# MCISO-S01-V00-Master.net
KiCad netlist of a schematic drawn in Altium Designer
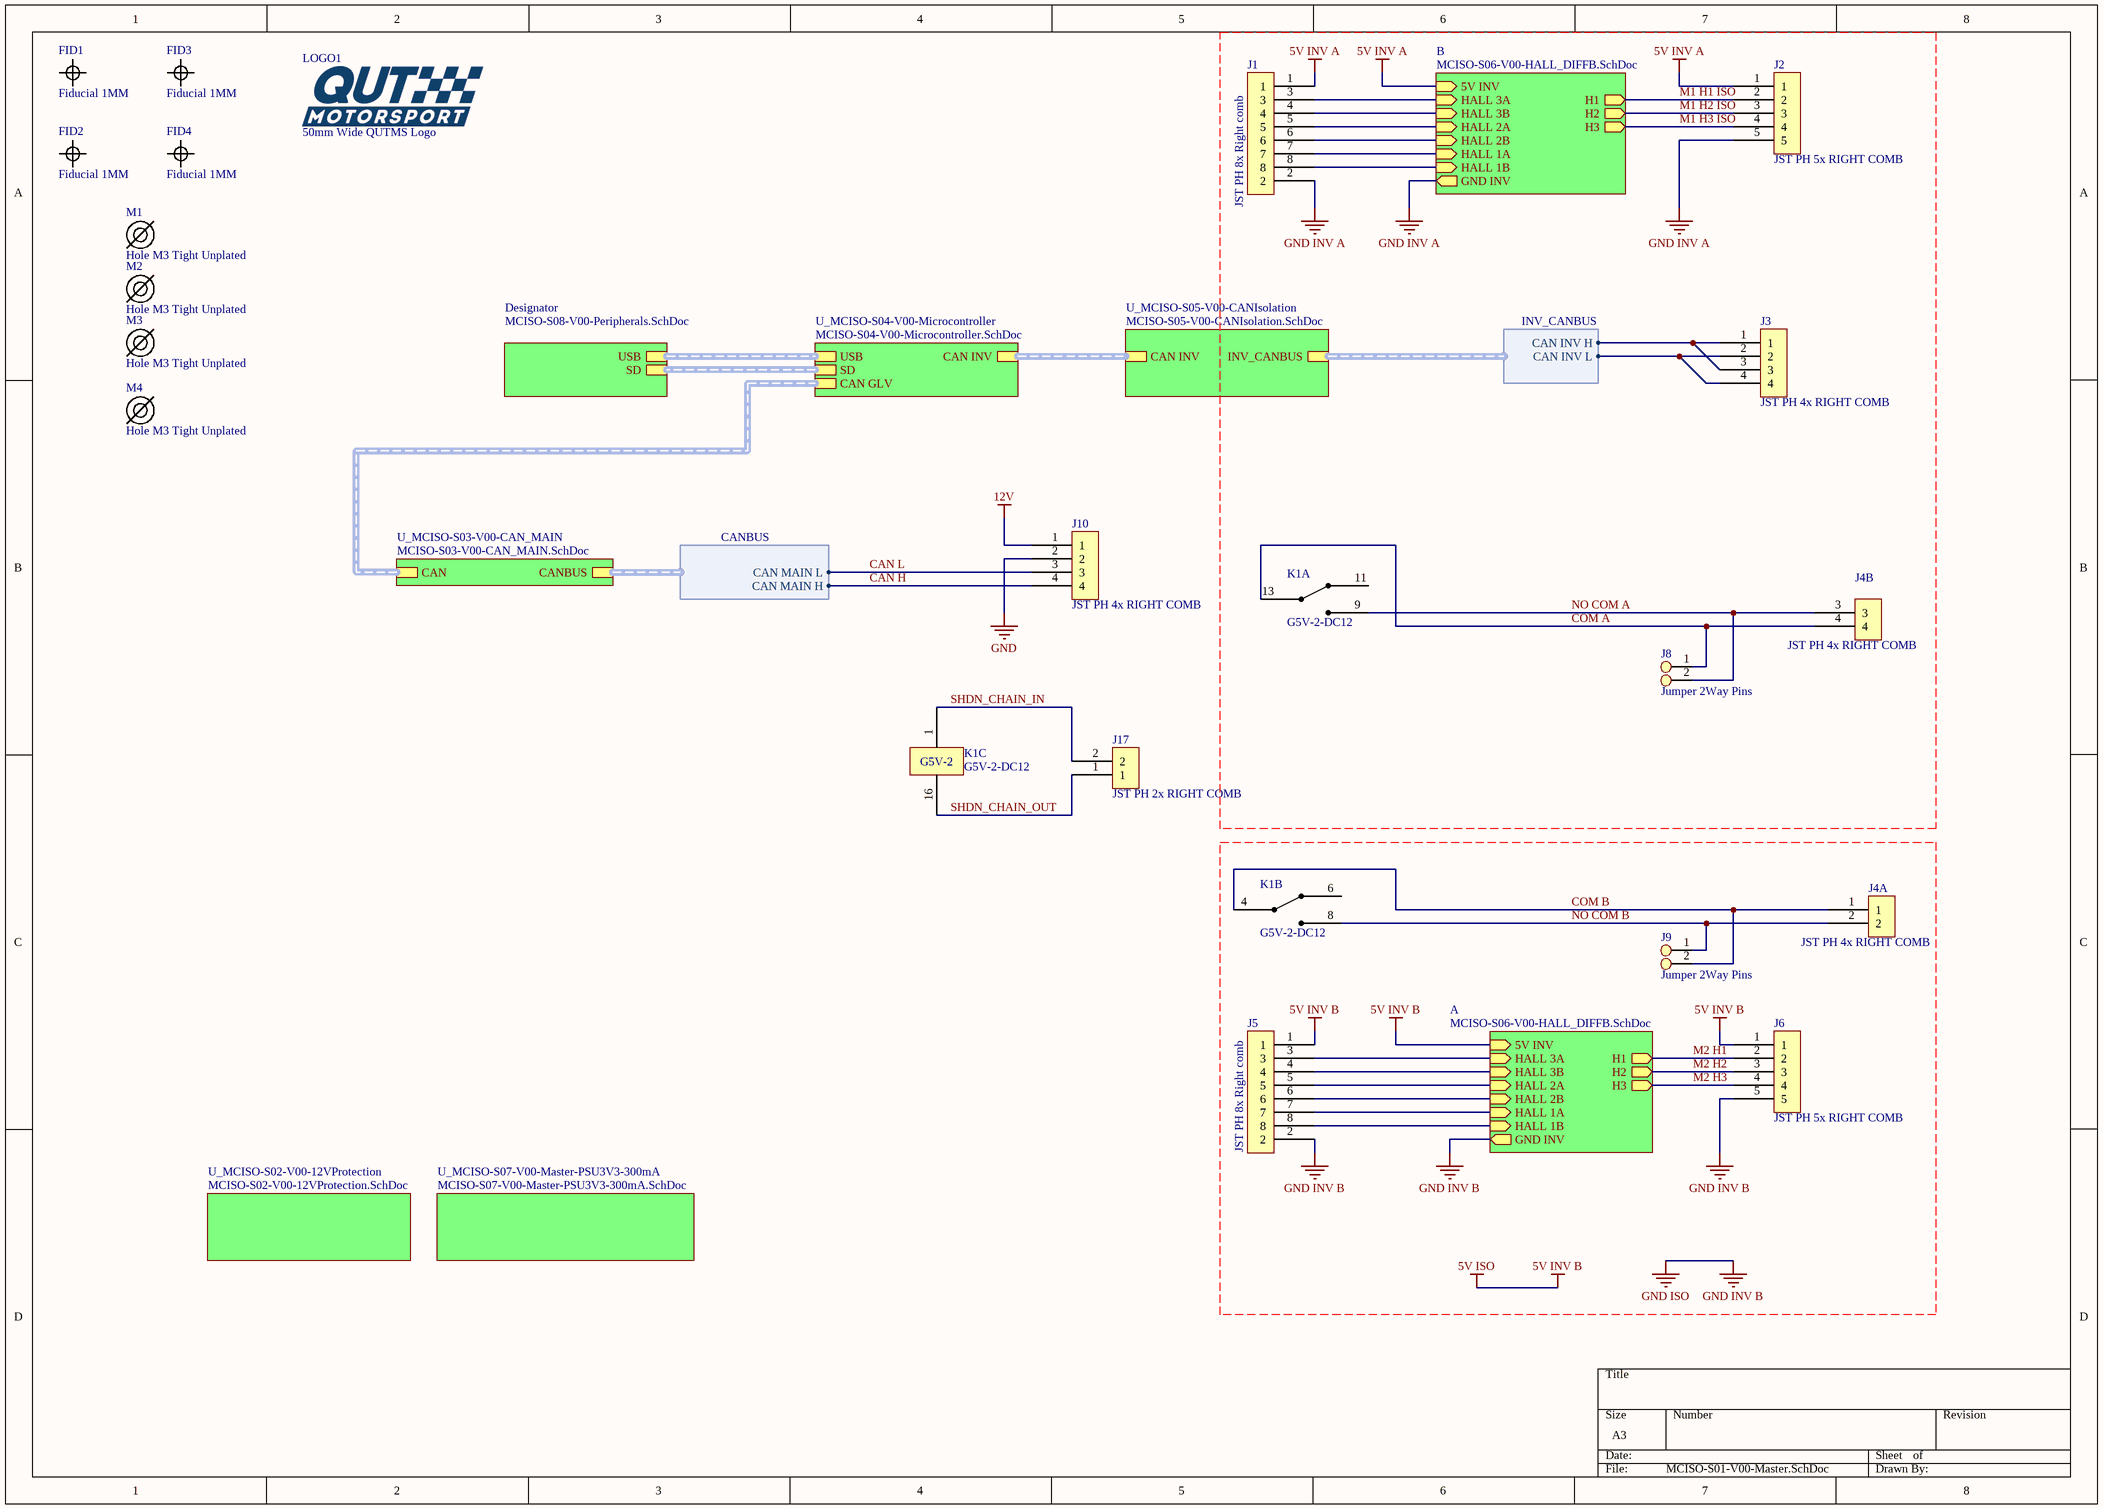
[diagram p0: MCISO-S01-V00-Master.SchDoc]

(export (version "E")
  (design (tool "Eeschema 10.0.6"))
  (components
    (comp (ref "FID1")
      (value "Fiducial 1MM")
      (footprint "FIDUCIAL 1MM")
      (libsource (lib "QUTMS-MCISOLibrary") (part "Fiducial 1MM"))
    )
    (comp (ref "FID2")
      (value "Fiducial 1MM")
      (footprint "FIDUCIAL 1MM")
      (libsource (lib "QUTMS-MCISOLibrary") (part "Fiducial 1MM"))
    )
    (comp (ref "FID3")
      (value "Fiducial 1MM")
      (footprint "FIDUCIAL 1MM")
      (libsource (lib "QUTMS-MCISOLibrary") (part "Fiducial 1MM"))
    )
    (comp (ref "FID4")
      (value "Fiducial 1MM")
      (footprint "FIDUCIAL 1MM")
      (libsource (lib "QUTMS-MCISOLibrary") (part "Fiducial 1MM"))
    )
    (comp (ref "J1")
      (value "JST PH 8x Right comb")
      (footprint "JST PH 8x RIGHT SMD")
      (libsource (lib "QUTMS-MCISOLibrary") (part "JST PH 8x Right comb"))
    )
    (comp (ref "J2")
      (value "JST PH 5x RIGHT COMB")
      (footprint "JST PH 5x RIGHT COMB")
      (libsource (lib "QUTMS-MCISOLibrary") (part "JST PH 5x RIGHT COMB"))
    )
    (comp (ref "J3")
      (value "JST PH 4x RIGHT COMB")
      (footprint "JST PH 4x RIGHT COMB")
      (libsource (lib "QUTMS-MCISOLibrary") (part "JST PH 4x RIGHT COMB"))
    )
    (comp (ref "J4")
      (value "JST PH 4x RIGHT COMB")
      (footprint "JST PH 4x RIGHT COMB")
      (libsource (lib "QUTMS-MCISOLibrary") (part "JST PH 4x RIGHT COMB_1"))
    )
    (comp (ref "J5")
      (value "JST PH 8x Right comb")
      (footprint "JST PH 8x RIGHT SMD")
      (libsource (lib "QUTMS-MCISOLibrary") (part "JST PH 8x Right comb"))
    )
    (comp (ref "J6")
      (value "JST PH 5x RIGHT COMB")
      (footprint "JST PH 5x RIGHT COMB")
      (libsource (lib "QUTMS-MCISOLibrary") (part "JST PH 5x RIGHT COMB"))
    )
    (comp (ref "J8")
      (value "Jumper 2Way Pins")
      (footprint "Jumper_2Way_Pin")
      (description "Jumper 2Way Side Pins")
      (libsource (lib "QUTMS-MCISOLibrary") (part "Jumper 2Way Side Pins"))
    )
    (comp (ref "J9")
      (value "Jumper 2Way Pins")
      (footprint "Jumper_2Way_Pin")
      (description "Jumper 2Way Side Pins")
      (libsource (lib "QUTMS-MCISOLibrary") (part "Jumper 2Way Side Pins"))
    )
    (comp (ref "J10")
      (value "JST PH 4x RIGHT COMB")
      (footprint "JST PH 4x RIGHT COMB")
      (libsource (lib "QUTMS-MCISOLibrary") (part "JST PH 4x RIGHT COMB"))
    )
    (comp (ref "J17")
      (value "JST PH 2x RIGHT COMB")
      (footprint "JST PH 2x RIGHT COMB")
      (libsource (lib "QUTMS-MCISOLibrary") (part "JST PH 2x RIGHT COMB"))
    )
    (comp (ref "K1")
      (value "G5V-2-DC12")
      (footprint "G5V-2")
      (description "General Purpose Relay DPDT (2 Form C) Through Hole, 12V, 2A")
      (libsource (lib "QUTMS-MCISOLibrary") (part "G5V-2-DC12"))
    )
    (comp (ref "LOGO1")
      (value "50mm Wide QUTMS Logo")
      (footprint "QUTMS LOGO 10MM")
      (libsource (lib "QUTMS-MCISOLibrary") (part "QUTMS Logo 50mm"))
    )
    (comp (ref "M1")
      (value "Hole M3 Tight Unplated")
      (footprint "M3.2 UNPLATED")
      (description "M3.2 Hole, No Plating")
      (libsource (lib "QUTMS-MCISOLibrary") (part "Hole M3 Tight Unplated"))
    )
    (comp (ref "M2")
      (value "Hole M3 Tight Unplated")
      (footprint "M3.2 UNPLATED")
      (description "M3.2 Hole, No Plating")
      (libsource (lib "QUTMS-MCISOLibrary") (part "Hole M3 Tight Unplated"))
    )
    (comp (ref "M3")
      (value "Hole M3 Tight Unplated")
      (footprint "M3.2 UNPLATED")
      (description "M3.2 Hole, No Plating")
      (libsource (lib "QUTMS-MCISOLibrary") (part "Hole M3 Tight Unplated"))
    )
    (comp (ref "M4")
      (value "Hole M3 Tight Unplated")
      (footprint "M3.2 UNPLATED")
      (description "M3.2 Hole, No Plating")
      (libsource (lib "QUTMS-MCISOLibrary") (part "Hole M3 Tight Unplated"))
    )
  )
  (nets
    (net (code "4") (name "/CAN H") (class "Default")
      (node (ref "J10") (pin "4") (pinfunction "4_4") (pintype "passive"))
    )
    (net (code "6") (name "/CAN L") (class "Default")
      (node (ref "J10") (pin "3") (pinfunction "3_3") (pintype "passive"))
    )
    (net (code "7") (name "/COM A") (class "Default")
      (node (ref "J4") (pin "4") (pinfunction "4_4") (pintype "passive"))
      (node (ref "J8") (pin "1") (pinfunction "1_1") (pintype "passive"))
      (node (ref "K1") (pin "13") (pinfunction "13_13") (pintype "passive"))
    )
    (net (code "8") (name "/COM B") (class "Default")
      (node (ref "J4") (pin "1") (pinfunction "1_1") (pintype "passive"))
      (node (ref "J9") (pin "2") (pinfunction "2_2") (pintype "passive"))
      (node (ref "K1") (pin "4") (pinfunction "4_4") (pintype "passive"))
    )
    (net (code "9") (name "/HALL 1A") (class "Default")
      (node (ref "J5") (pin "7") (pinfunction "7_7") (pintype "passive"))
    )
    (net (code "10") (name "/HALL 1A_1") (class "Default")
      (node (ref "J1") (pin "7") (pinfunction "7_7") (pintype "passive"))
    )
    (net (code "11") (name "/HALL 1B") (class "Default")
      (node (ref "J5") (pin "8") (pinfunction "8_8") (pintype "passive"))
    )
    (net (code "12") (name "/HALL 1B_1") (class "Default")
      (node (ref "J1") (pin "8") (pinfunction "8_8") (pintype "passive"))
    )
    (net (code "13") (name "/HALL 2A") (class "Default")
      (node (ref "J5") (pin "5") (pinfunction "5_5") (pintype "passive"))
    )
    (net (code "14") (name "/HALL 2A_1") (class "Default")
      (node (ref "J1") (pin "5") (pinfunction "5_5") (pintype "passive"))
    )
    (net (code "15") (name "/HALL 2B") (class "Default")
      (node (ref "J5") (pin "6") (pinfunction "6_6") (pintype "passive"))
    )
    (net (code "16") (name "/HALL 2B_1") (class "Default")
      (node (ref "J1") (pin "6") (pinfunction "6_6") (pintype "passive"))
    )
    (net (code "17") (name "/HALL 3A") (class "Default")
      (node (ref "J5") (pin "3") (pinfunction "3_3") (pintype "passive"))
    )
    (net (code "18") (name "/HALL 3A_1") (class "Default")
      (node (ref "J1") (pin "3") (pinfunction "3_3") (pintype "passive"))
    )
    (net (code "19") (name "/HALL 3B") (class "Default")
      (node (ref "J5") (pin "4") (pinfunction "4_4") (pintype "passive"))
    )
    (net (code "20") (name "/HALL 3B_1") (class "Default")
      (node (ref "J1") (pin "4") (pinfunction "4_4") (pintype "passive"))
    )
    (net (code "21") (name "/M1 H1 ISO") (class "Default")
      (node (ref "J2") (pin "2") (pinfunction "2_2") (pintype "passive"))
    )
    (net (code "22") (name "/M1 H2 ISO") (class "Default")
      (node (ref "J2") (pin "3") (pinfunction "3_3") (pintype "passive"))
    )
    (net (code "23") (name "/M1 H3 ISO") (class "Default")
      (node (ref "J2") (pin "4") (pinfunction "4_4") (pintype "passive"))
    )
    (net (code "24") (name "/M2 H1") (class "Default")
      (node (ref "J6") (pin "2") (pinfunction "2_2") (pintype "passive"))
    )
    (net (code "25") (name "/M2 H2") (class "Default")
      (node (ref "J6") (pin "3") (pinfunction "3_3") (pintype "passive"))
    )
    (net (code "26") (name "/M2 H3") (class "Default")
      (node (ref "J6") (pin "4") (pinfunction "4_4") (pintype "passive"))
    )
    (net (code "27") (name "/NO COM A") (class "Default")
      (node (ref "J4") (pin "3") (pinfunction "3_3") (pintype "passive"))
      (node (ref "J8") (pin "2") (pinfunction "2_2") (pintype "passive"))
      (node (ref "K1") (pin "9") (pinfunction "9_9") (pintype "passive"))
    )
    (net (code "28") (name "/NO COM B") (class "Default")
      (node (ref "J4") (pin "2") (pinfunction "2_2") (pintype "passive"))
      (node (ref "J9") (pin "1") (pinfunction "1_1") (pintype "passive"))
      (node (ref "K1") (pin "8") (pinfunction "8_8") (pintype "passive"))
    )
    (net (code "30") (name "/SHDN_CHAIN_IN") (class "Default")
      (node (ref "J17") (pin "2") (pinfunction "2_2") (pintype "passive"))
      (node (ref "K1") (pin "1") (pinfunction "1_1") (pintype "passive"))
    )
    (net (code "31") (name "/SHDN_CHAIN_OUT") (class "Default")
      (node (ref "J17") (pin "1") (pinfunction "1_1") (pintype "passive"))
      (node (ref "K1") (pin "16") (pinfunction "16_16") (pintype "passive"))
    )
    (net (code "35") (name "5V INV A") (class "Default")
      (node (ref "J1") (pin "1") (pinfunction "1_1") (pintype "passive"))
      (node (ref "J2") (pin "1") (pinfunction "1_1") (pintype "passive"))
    )
    (net (code "36") (name "5V INV B") (class "Default")
      (node (ref "J5") (pin "1") (pinfunction "1_1") (pintype "passive"))
      (node (ref "J6") (pin "1") (pinfunction "1_1") (pintype "passive"))
    )
    (net (code "37") (name "12V") (class "Default")
      (node (ref "J10") (pin "1") (pinfunction "1_1") (pintype "passive"))
    )
    (net (code "38") (name "GND") (class "Default")
      (node (ref "J10") (pin "2") (pinfunction "2_2") (pintype "passive"))
    )
    (net (code "39") (name "GND INV A") (class "Default")
      (node (ref "J1") (pin "2") (pinfunction "2_2") (pintype "passive"))
      (node (ref "J2") (pin "5") (pinfunction "5_5") (pintype "passive"))
    )
    (net (code "40") (name "GND INV B") (class "Default")
      (node (ref "J5") (pin "2") (pinfunction "2_2") (pintype "passive"))
      (node (ref "J6") (pin "5") (pinfunction "5_5") (pintype "passive"))
    )
    (net (code "41") (name "Net-(J3-Pad1)") (class "Default")
      (node (ref "J3") (pin "1") (pinfunction "1_1") (pintype "passive"))
      (node (ref "J3") (pin "3") (pinfunction "3_3") (pintype "passive"))
    )
    (net (code "42") (name "Net-(J3-Pad2)") (class "Default")
      (node (ref "J3") (pin "2") (pinfunction "2_2") (pintype "passive"))
      (node (ref "J3") (pin "4") (pinfunction "4_4") (pintype "passive"))
    )
    (net (code "43") (name "unconnected-(K1-Pad6)") (class "Default")
      (node (ref "K1") (pin "6") (pinfunction "6_6") (pintype "passive"))
    )
    (net (code "44") (name "unconnected-(K1-Pad11)") (class "Default")
      (node (ref "K1") (pin "11") (pinfunction "11_11") (pintype "passive"))
    )
  )
)
